# Electronics-final.net
KiCad netlist of a schematic drawn in EAGLE
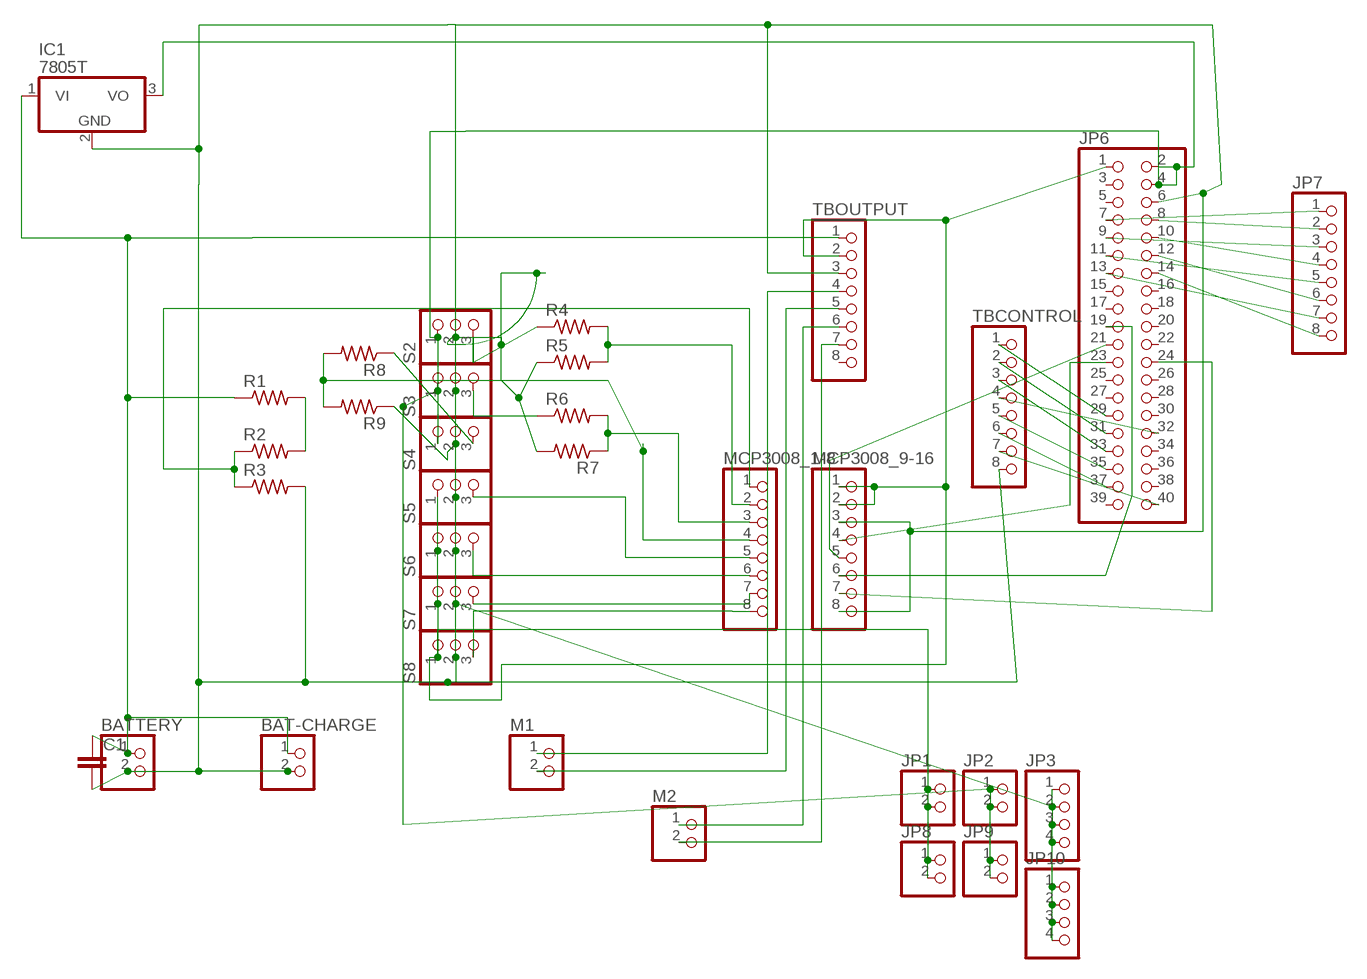
[diagram p0: schematic, sheet 1]

(export (version "E")
  (design (tool "Eeschema 10.0.6"))
  (components
    (comp (ref "BAT-CHARGE")
      (value "PINHD-1X2")
      (footprint "eagle-import:1X02")
      (libsource (lib "eagle-import") (part "PINHD-1X2"))
    )
    (comp (ref "BATTERY")
      (value "PINHD-1X2")
      (footprint "eagle-import:1X02")
      (libsource (lib "eagle-import") (part "PINHD-1X2"))
    )
    (comp (ref "C1")
      (value "C-EU050-035X075")
      (footprint "eagle-import:C050-035X075")
      (libsource (lib "eagle-import") (part "C-EU050-035X075"))
    )
    (comp (ref "IC1")
      (value "7805T")
      (footprint "eagle-import:TO220H")
      (libsource (lib "eagle-import") (part "78T05"))
    )
    (comp (ref "JP1")
      (value "PINHD-1X2")
      (footprint "eagle-import:1X02")
      (libsource (lib "eagle-import") (part "PINHD-1X2"))
    )
    (comp (ref "JP2")
      (value "PINHD-1X2")
      (footprint "eagle-import:1X02")
      (libsource (lib "eagle-import") (part "PINHD-1X2"))
    )
    (comp (ref "JP3")
      (value "PINHD-1X4")
      (footprint "eagle-import:1X04")
      (libsource (lib "eagle-import") (part "PINHD-1X4"))
    )
    (comp (ref "JP6")
      (value "PINHD-2X20")
      (footprint "eagle-import:2X20")
      (libsource (lib "eagle-import") (part "PINHD-2X20"))
    )
    (comp (ref "JP7")
      (value "PINHD-1X8")
      (footprint "eagle-import:1X08")
      (libsource (lib "eagle-import") (part "PINHD-1X8"))
    )
    (comp (ref "JP8")
      (value "PINHD-1X2")
      (footprint "eagle-import:1X02")
      (libsource (lib "eagle-import") (part "PINHD-1X2"))
    )
    (comp (ref "JP9")
      (value "PINHD-1X2")
      (footprint "eagle-import:1X02")
      (libsource (lib "eagle-import") (part "PINHD-1X2"))
    )
    (comp (ref "JP10")
      (value "PINHD-1X4")
      (footprint "eagle-import:1X04")
      (libsource (lib "eagle-import") (part "PINHD-1X4"))
    )
    (comp (ref "M1")
      (value "PINHD-1X2")
      (footprint "eagle-import:1X02")
      (libsource (lib "eagle-import") (part "PINHD-1X2"))
    )
    (comp (ref "M2")
      (value "PINHD-1X2")
      (footprint "eagle-import:1X02")
      (libsource (lib "eagle-import") (part "PINHD-1X2"))
    )
    (comp (ref "MCP3008_1-8")
      (value "PINHD-1X8")
      (footprint "eagle-import:1X08")
      (libsource (lib "eagle-import") (part "PINHD-1X8"))
    )
    (comp (ref "MCP3008_9-16")
      (value "PINHD-1X8")
      (footprint "eagle-import:1X08")
      (libsource (lib "eagle-import") (part "PINHD-1X8"))
    )
    (comp (ref "R1")
      (value "R-US_0204/7")
      (footprint "eagle-import:0204_7")
      (libsource (lib "eagle-import") (part "R-US_0204/7"))
    )
    (comp (ref "R2")
      (value "R-US_0204/7")
      (footprint "eagle-import:0204_7")
      (libsource (lib "eagle-import") (part "R-US_0204/7"))
    )
    (comp (ref "R3")
      (value "R-US_0204/7")
      (footprint "eagle-import:0204_7")
      (libsource (lib "eagle-import") (part "R-US_0204/7"))
    )
    (comp (ref "R4")
      (value "R-US_0204/7")
      (footprint "eagle-import:0204_7")
      (libsource (lib "eagle-import") (part "R-US_0204/7"))
    )
    (comp (ref "R5")
      (value "R-US_0204/7")
      (footprint "eagle-import:0204_7")
      (libsource (lib "eagle-import") (part "R-US_0204/7"))
    )
    (comp (ref "R6")
      (value "R-US_0204/7")
      (footprint "eagle-import:0204_7")
      (libsource (lib "eagle-import") (part "R-US_0204/7"))
    )
    (comp (ref "R7")
      (value "R-US_0204/7")
      (footprint "eagle-import:0204_7")
      (libsource (lib "eagle-import") (part "R-US_0204/7"))
    )
    (comp (ref "R8")
      (value "R-US_0204/7")
      (footprint "eagle-import:0204_7")
      (libsource (lib "eagle-import") (part "R-US_0204/7"))
    )
    (comp (ref "R9")
      (value "R-US_0204/7")
      (footprint "eagle-import:0204_7")
      (libsource (lib "eagle-import") (part "R-US_0204/7"))
    )
    (comp (ref "S2")
      (value "PINHD-1X3")
      (footprint "eagle-import:1X03")
      (libsource (lib "eagle-import") (part "PINHD-1X3"))
    )
    (comp (ref "S3")
      (value "PINHD-1X3")
      (footprint "eagle-import:1X03")
      (libsource (lib "eagle-import") (part "PINHD-1X3"))
    )
    (comp (ref "S4")
      (value "PINHD-1X3")
      (footprint "eagle-import:1X03")
      (libsource (lib "eagle-import") (part "PINHD-1X3"))
    )
    (comp (ref "S5")
      (value "PINHD-1X3")
      (footprint "eagle-import:1X03")
      (libsource (lib "eagle-import") (part "PINHD-1X3"))
    )
    (comp (ref "S6")
      (value "PINHD-1X3")
      (footprint "eagle-import:1X03")
      (libsource (lib "eagle-import") (part "PINHD-1X3"))
    )
    (comp (ref "S7")
      (value "PINHD-1X3")
      (footprint "eagle-import:1X03")
      (libsource (lib "eagle-import") (part "PINHD-1X3"))
    )
    (comp (ref "S8")
      (value "PINHD-1X3")
      (footprint "eagle-import:1X03")
      (libsource (lib "eagle-import") (part "PINHD-1X3"))
    )
    (comp (ref "TBCONTROL")
      (value "PINHD-1X8")
      (footprint "eagle-import:1X08")
      (libsource (lib "eagle-import") (part "PINHD-1X8"))
    )
    (comp (ref "TBOUTPUT")
      (value "PINHD-1X8")
      (footprint "eagle-import:1X08")
      (libsource (lib "eagle-import") (part "PINHD-1X8"))
    )
  )
  (nets
    (net (code "1") (name "Net-(IC1-GND)") (class "Default")
      (node (ref "BAT-CHARGE") (pin "2") (pinfunction "2_2") (pintype "passive"))
      (node (ref "BATTERY") (pin "2") (pinfunction "2_2") (pintype "passive"))
      (node (ref "C1") (pin "2") (pinfunction "2_2") (pintype "passive"))
      (node (ref "IC1") (pin "2") (pinfunction "GND_2") (pintype "passive"))
      (node (ref "JP10") (pin "1") (pinfunction "1_1") (pintype "passive"))
      (node (ref "JP10") (pin "2") (pinfunction "2_2") (pintype "passive"))
      (node (ref "JP10") (pin "3") (pinfunction "3_3") (pintype "passive"))
      (node (ref "JP10") (pin "4") (pinfunction "4_4") (pintype "passive"))
      (node (ref "JP3") (pin "1") (pinfunction "1_1") (pintype "passive"))
      (node (ref "JP3") (pin "2") (pinfunction "2_2") (pintype "passive"))
      (node (ref "JP3") (pin "3") (pinfunction "3_3") (pintype "passive"))
      (node (ref "JP3") (pin "4") (pinfunction "4_4") (pintype "passive"))
      (node (ref "JP6") (pin "6") (pinfunction "6_6") (pintype "passive"))
      (node (ref "MCP3008_9-16") (pin "3") (pinfunction "3_3") (pintype "passive"))
      (node (ref "MCP3008_9-16") (pin "8") (pinfunction "8_8") (pintype "passive"))
      (node (ref "R3") (pin "2") (pinfunction "2_2") (pintype "passive"))
      (node (ref "R5") (pin "1") (pinfunction "1_1") (pintype "passive"))
      (node (ref "R7") (pin "2") (pinfunction "2_2") (pintype "passive"))
      (node (ref "R9") (pin "1") (pinfunction "1_1") (pintype "passive"))
      (node (ref "S2") (pin "2") (pinfunction "2_2") (pintype "passive"))
      (node (ref "S3") (pin "2") (pinfunction "2_2") (pintype "passive"))
      (node (ref "S4") (pin "2") (pinfunction "2_2") (pintype "passive"))
      (node (ref "S5") (pin "2") (pinfunction "2_2") (pintype "passive"))
      (node (ref "S6") (pin "2") (pinfunction "2_2") (pintype "passive"))
      (node (ref "S7") (pin "2") (pinfunction "2_2") (pintype "passive"))
      (node (ref "S8") (pin "2") (pinfunction "2_2") (pintype "passive"))
      (node (ref "TBCONTROL") (pin "8") (pinfunction "8_8") (pintype "passive"))
      (node (ref "TBOUTPUT") (pin "3") (pinfunction "3_3") (pintype "passive"))
    )
    (net (code "2") (name "Net-(IC1-VI)") (class "Default")
      (node (ref "BAT-CHARGE") (pin "1") (pinfunction "1_1") (pintype "passive"))
      (node (ref "BATTERY") (pin "1") (pinfunction "1_1") (pintype "passive"))
      (node (ref "C1") (pin "1") (pinfunction "1_1") (pintype "passive"))
      (node (ref "IC1") (pin "1") (pinfunction "VI_1") (pintype "input"))
      (node (ref "R1") (pin "1") (pinfunction "1_1") (pintype "passive"))
      (node (ref "TBOUTPUT") (pin "1") (pinfunction "1_1") (pintype "passive"))
    )
    (net (code "3") (name "Net-(IC1-VO)") (class "Default")
      (node (ref "IC1") (pin "3") (pinfunction "VO_3") (pintype "passive"))
      (node (ref "JP2") (pin "1") (pinfunction "1_1") (pintype "passive"))
      (node (ref "JP2") (pin "2") (pinfunction "2_2") (pintype "passive"))
      (node (ref "JP6") (pin "2") (pinfunction "2_2") (pintype "passive"))
      (node (ref "JP6") (pin "4") (pinfunction "4_4") (pintype "passive"))
      (node (ref "JP9") (pin "1") (pinfunction "1_1") (pintype "passive"))
      (node (ref "JP9") (pin "2") (pinfunction "2_2") (pintype "passive"))
      (node (ref "S2") (pin "1") (pinfunction "1_1") (pintype "passive"))
      (node (ref "S3") (pin "1") (pinfunction "1_1") (pintype "passive"))
      (node (ref "S4") (pin "1") (pinfunction "1_1") (pintype "passive"))
    )
    (net (code "4") (name "Net-(JP1-Pad1)") (class "Default")
      (node (ref "JP1") (pin "1") (pinfunction "1_1") (pintype "passive"))
      (node (ref "JP1") (pin "2") (pinfunction "2_2") (pintype "passive"))
      (node (ref "JP6") (pin "1") (pinfunction "1_1") (pintype "passive"))
      (node (ref "JP8") (pin "1") (pinfunction "1_1") (pintype "passive"))
      (node (ref "JP8") (pin "2") (pinfunction "2_2") (pintype "passive"))
      (node (ref "MCP3008_9-16") (pin "1") (pinfunction "1_1") (pintype "passive"))
      (node (ref "MCP3008_9-16") (pin "2") (pinfunction "2_2") (pintype "passive"))
      (node (ref "S5") (pin "1") (pinfunction "1_1") (pintype "passive"))
      (node (ref "S6") (pin "1") (pinfunction "1_1") (pintype "passive"))
      (node (ref "S7") (pin "1") (pinfunction "1_1") (pintype "passive"))
      (node (ref "S8") (pin "1") (pinfunction "1_1") (pintype "passive"))
      (node (ref "TBOUTPUT") (pin "2") (pinfunction "2_2") (pintype "passive"))
    )
    (net (code "5") (name "Net-(JP6-Pad7)") (class "Default")
      (node (ref "JP6") (pin "7") (pinfunction "7_7") (pintype "passive"))
      (node (ref "JP7") (pin "1") (pinfunction "1_1") (pintype "passive"))
    )
    (net (code "6") (name "Net-(JP6-Pad8)") (class "Default")
      (node (ref "JP6") (pin "8") (pinfunction "8_8") (pintype "passive"))
      (node (ref "JP7") (pin "2") (pinfunction "2_2") (pintype "passive"))
    )
    (net (code "7") (name "Net-(JP6-Pad9)") (class "Default")
      (node (ref "JP6") (pin "9") (pinfunction "9_9") (pintype "passive"))
      (node (ref "JP7") (pin "3") (pinfunction "3_3") (pintype "passive"))
    )
    (net (code "8") (name "Net-(JP6-Pad10)") (class "Default")
      (node (ref "JP6") (pin "10") (pinfunction "10_10") (pintype "passive"))
      (node (ref "JP7") (pin "4") (pinfunction "4_4") (pintype "passive"))
    )
    (net (code "9") (name "Net-(JP6-Pad11)") (class "Default")
      (node (ref "JP6") (pin "11") (pinfunction "11_11") (pintype "passive"))
      (node (ref "JP7") (pin "5") (pinfunction "5_5") (pintype "passive"))
    )
    (net (code "10") (name "Net-(JP6-Pad12)") (class "Default")
      (node (ref "JP6") (pin "12") (pinfunction "12_12") (pintype "passive"))
      (node (ref "JP7") (pin "6") (pinfunction "6_6") (pintype "passive"))
    )
    (net (code "11") (name "Net-(JP6-Pad13)") (class "Default")
      (node (ref "JP6") (pin "13") (pinfunction "13_13") (pintype "passive"))
      (node (ref "JP7") (pin "7") (pinfunction "7_7") (pintype "passive"))
    )
    (net (code "12") (name "Net-(JP6-Pad14)") (class "Default")
      (node (ref "JP6") (pin "14") (pinfunction "14_14") (pintype "passive"))
      (node (ref "JP7") (pin "8") (pinfunction "8_8") (pintype "passive"))
    )
    (net (code "13") (name "Net-(JP6-Pad19)") (class "Default")
      (node (ref "JP6") (pin "19") (pinfunction "19_19") (pintype "passive"))
      (node (ref "MCP3008_9-16") (pin "6") (pinfunction "6_6") (pintype "passive"))
    )
    (net (code "14") (name "Net-(JP6-Pad21)") (class "Default")
      (node (ref "JP6") (pin "21") (pinfunction "21_21") (pintype "passive"))
      (node (ref "MCP3008_9-16") (pin "5") (pinfunction "5_5") (pintype "passive"))
    )
    (net (code "15") (name "Net-(JP6-Pad23)") (class "Default")
      (node (ref "JP6") (pin "23") (pinfunction "23_23") (pintype "passive"))
      (node (ref "MCP3008_9-16") (pin "4") (pinfunction "4_4") (pintype "passive"))
    )
    (net (code "16") (name "Net-(JP6-Pad24)") (class "Default")
      (node (ref "JP6") (pin "24") (pinfunction "24_24") (pintype "passive"))
      (node (ref "MCP3008_9-16") (pin "7") (pinfunction "7_7") (pintype "passive"))
    )
    (net (code "17") (name "Net-(JP6-Pad29)") (class "Default")
      (node (ref "JP6") (pin "29") (pinfunction "29_29") (pintype "passive"))
      (node (ref "TBCONTROL") (pin "1") (pinfunction "1_1") (pintype "passive"))
    )
    (net (code "18") (name "Net-(JP6-Pad31)") (class "Default")
      (node (ref "JP6") (pin "31") (pinfunction "31_31") (pintype "passive"))
      (node (ref "TBCONTROL") (pin "2") (pinfunction "2_2") (pintype "passive"))
    )
    (net (code "19") (name "Net-(JP6-Pad32)") (class "Default")
      (node (ref "JP6") (pin "32") (pinfunction "32_32") (pintype "passive"))
      (node (ref "TBCONTROL") (pin "4") (pinfunction "4_4") (pintype "passive"))
    )
    (net (code "20") (name "Net-(JP6-Pad33)") (class "Default")
      (node (ref "JP6") (pin "33") (pinfunction "33_33") (pintype "passive"))
      (node (ref "TBCONTROL") (pin "3") (pinfunction "3_3") (pintype "passive"))
    )
    (net (code "21") (name "Net-(JP6-Pad35)") (class "Default")
      (node (ref "JP6") (pin "35") (pinfunction "35_35") (pintype "passive"))
      (node (ref "TBCONTROL") (pin "5") (pinfunction "5_5") (pintype "passive"))
    )
    (net (code "22") (name "Net-(JP6-Pad37)") (class "Default")
      (node (ref "JP6") (pin "37") (pinfunction "37_37") (pintype "passive"))
      (node (ref "TBCONTROL") (pin "6") (pinfunction "6_6") (pintype "passive"))
    )
    (net (code "23") (name "Net-(JP6-Pad40)") (class "Default")
      (node (ref "JP6") (pin "40") (pinfunction "40_40") (pintype "passive"))
      (node (ref "TBCONTROL") (pin "7") (pinfunction "7_7") (pintype "passive"))
    )
    (net (code "24") (name "Net-(M1-Pad1)") (class "Default")
      (node (ref "M1") (pin "1") (pinfunction "1_1") (pintype "passive"))
      (node (ref "TBOUTPUT") (pin "4") (pinfunction "4_4") (pintype "passive"))
    )
    (net (code "25") (name "Net-(M1-Pad2)") (class "Default")
      (node (ref "M1") (pin "2") (pinfunction "2_2") (pintype "passive"))
      (node (ref "TBOUTPUT") (pin "5") (pinfunction "5_5") (pintype "passive"))
    )
    (net (code "26") (name "Net-(M2-Pad1)") (class "Default")
      (node (ref "M2") (pin "1") (pinfunction "1_1") (pintype "passive"))
      (node (ref "TBOUTPUT") (pin "6") (pinfunction "6_6") (pintype "passive"))
    )
    (net (code "27") (name "Net-(M2-Pad2)") (class "Default")
      (node (ref "M2") (pin "2") (pinfunction "2_2") (pintype "passive"))
      (node (ref "TBOUTPUT") (pin "7") (pinfunction "7_7") (pintype "passive"))
    )
    (net (code "28") (name "Net-(MCP3008_1-8-Pad1)") (class "Default")
      (node (ref "MCP3008_1-8") (pin "1") (pinfunction "1_1") (pintype "passive"))
      (node (ref "R2") (pin "1") (pinfunction "1_1") (pintype "passive"))
      (node (ref "R3") (pin "1") (pinfunction "1_1") (pintype "passive"))
    )
    (net (code "29") (name "Net-(MCP3008_1-8-Pad2)") (class "Default")
      (node (ref "MCP3008_1-8") (pin "2") (pinfunction "2_2") (pintype "passive"))
      (node (ref "R4") (pin "2") (pinfunction "2_2") (pintype "passive"))
      (node (ref "R5") (pin "2") (pinfunction "2_2") (pintype "passive"))
    )
    (net (code "30") (name "Net-(MCP3008_1-8-Pad3)") (class "Default")
      (node (ref "MCP3008_1-8") (pin "3") (pinfunction "3_3") (pintype "passive"))
      (node (ref "R6") (pin "2") (pinfunction "2_2") (pintype "passive"))
      (node (ref "R7") (pin "1") (pinfunction "1_1") (pintype "passive"))
    )
    (net (code "31") (name "Net-(MCP3008_1-8-Pad4)") (class "Default")
      (node (ref "MCP3008_1-8") (pin "4") (pinfunction "4_4") (pintype "passive"))
      (node (ref "R8") (pin "2") (pinfunction "2_2") (pintype "passive"))
      (node (ref "R9") (pin "2") (pinfunction "2_2") (pintype "passive"))
    )
    (net (code "32") (name "Net-(MCP3008_1-8-Pad5)") (class "Default")
      (node (ref "MCP3008_1-8") (pin "5") (pinfunction "5_5") (pintype "passive"))
      (node (ref "S5") (pin "3") (pinfunction "3_3") (pintype "passive"))
    )
    (net (code "33") (name "Net-(MCP3008_1-8-Pad6)") (class "Default")
      (node (ref "MCP3008_1-8") (pin "6") (pinfunction "6_6") (pintype "passive"))
      (node (ref "S6") (pin "3") (pinfunction "3_3") (pintype "passive"))
    )
    (net (code "34") (name "Net-(MCP3008_1-8-Pad7)") (class "Default")
      (node (ref "MCP3008_1-8") (pin "7") (pinfunction "7_7") (pintype "passive"))
      (node (ref "S7") (pin "3") (pinfunction "3_3") (pintype "passive"))
    )
    (net (code "35") (name "Net-(MCP3008_1-8-Pad8)") (class "Default")
      (node (ref "MCP3008_1-8") (pin "8") (pinfunction "8_8") (pintype "passive"))
      (node (ref "S8") (pin "3") (pinfunction "3_3") (pintype "passive"))
    )
    (net (code "36") (name "Net-(R1-Pad2)") (class "Default")
      (node (ref "R1") (pin "2") (pinfunction "2_2") (pintype "passive"))
      (node (ref "R2") (pin "2") (pinfunction "2_2") (pintype "passive"))
    )
    (net (code "37") (name "Net-(R4-Pad1)") (class "Default")
      (node (ref "R4") (pin "1") (pinfunction "1_1") (pintype "passive"))
      (node (ref "S2") (pin "3") (pinfunction "3_3") (pintype "passive"))
    )
    (net (code "38") (name "Net-(R6-Pad1)") (class "Default")
      (node (ref "R6") (pin "1") (pinfunction "1_1") (pintype "passive"))
      (node (ref "S3") (pin "3") (pinfunction "3_3") (pintype "passive"))
    )
    (net (code "39") (name "Net-(R8-Pad1)") (class "Default")
      (node (ref "R8") (pin "1") (pinfunction "1_1") (pintype "passive"))
      (node (ref "S4") (pin "3") (pinfunction "3_3") (pintype "passive"))
    )
    (net (code "40") (name "unconnected-(JP6-Pad3)") (class "Default")
      (node (ref "JP6") (pin "3") (pinfunction "3_3") (pintype "passive"))
    )
    (net (code "41") (name "unconnected-(JP6-Pad5)") (class "Default")
      (node (ref "JP6") (pin "5") (pinfunction "5_5") (pintype "passive"))
    )
    (net (code "42") (name "unconnected-(JP6-Pad15)") (class "Default")
      (node (ref "JP6") (pin "15") (pinfunction "15_15") (pintype "passive"))
    )
    (net (code "43") (name "unconnected-(JP6-Pad16)") (class "Default")
      (node (ref "JP6") (pin "16") (pinfunction "16_16") (pintype "passive"))
    )
    (net (code "44") (name "unconnected-(JP6-Pad17)") (class "Default")
      (node (ref "JP6") (pin "17") (pinfunction "17_17") (pintype "passive"))
    )
    (net (code "45") (name "unconnected-(JP6-Pad18)") (class "Default")
      (node (ref "JP6") (pin "18") (pinfunction "18_18") (pintype "passive"))
    )
    (net (code "46") (name "unconnected-(JP6-Pad20)") (class "Default")
      (node (ref "JP6") (pin "20") (pinfunction "20_20") (pintype "passive"))
    )
    (net (code "47") (name "unconnected-(JP6-Pad22)") (class "Default")
      (node (ref "JP6") (pin "22") (pinfunction "22_22") (pintype "passive"))
    )
    (net (code "48") (name "unconnected-(JP6-Pad25)") (class "Default")
      (node (ref "JP6") (pin "25") (pinfunction "25_25") (pintype "passive"))
    )
    (net (code "49") (name "unconnected-(JP6-Pad26)") (class "Default")
      (node (ref "JP6") (pin "26") (pinfunction "26_26") (pintype "passive"))
    )
    (net (code "50") (name "unconnected-(JP6-Pad27)") (class "Default")
      (node (ref "JP6") (pin "27") (pinfunction "27_27") (pintype "passive"))
    )
    (net (code "51") (name "unconnected-(JP6-Pad28)") (class "Default")
      (node (ref "JP6") (pin "28") (pinfunction "28_28") (pintype "passive"))
    )
    (net (code "52") (name "unconnected-(JP6-Pad30)") (class "Default")
      (node (ref "JP6") (pin "30") (pinfunction "30_30") (pintype "passive"))
    )
    (net (code "53") (name "unconnected-(JP6-Pad34)") (class "Default")
      (node (ref "JP6") (pin "34") (pinfunction "34_34") (pintype "passive"))
    )
    (net (code "54") (name "unconnected-(JP6-Pad36)") (class "Default")
      (node (ref "JP6") (pin "36") (pinfunction "36_36") (pintype "passive"))
    )
    (net (code "55") (name "unconnected-(JP6-Pad38)") (class "Default")
      (node (ref "JP6") (pin "38") (pinfunction "38_38") (pintype "passive"))
    )
    (net (code "56") (name "unconnected-(JP6-Pad39)") (class "Default")
      (node (ref "JP6") (pin "39") (pinfunction "39_39") (pintype "passive"))
    )
    (net (code "57") (name "unconnected-(TBOUTPUT-Pad8)") (class "Default")
      (node (ref "TBOUTPUT") (pin "8") (pinfunction "8_8") (pintype "passive"))
    )
  )
)
